# Schematic.net
KiCad netlist of a schematic drawn in EasyEDA Pro
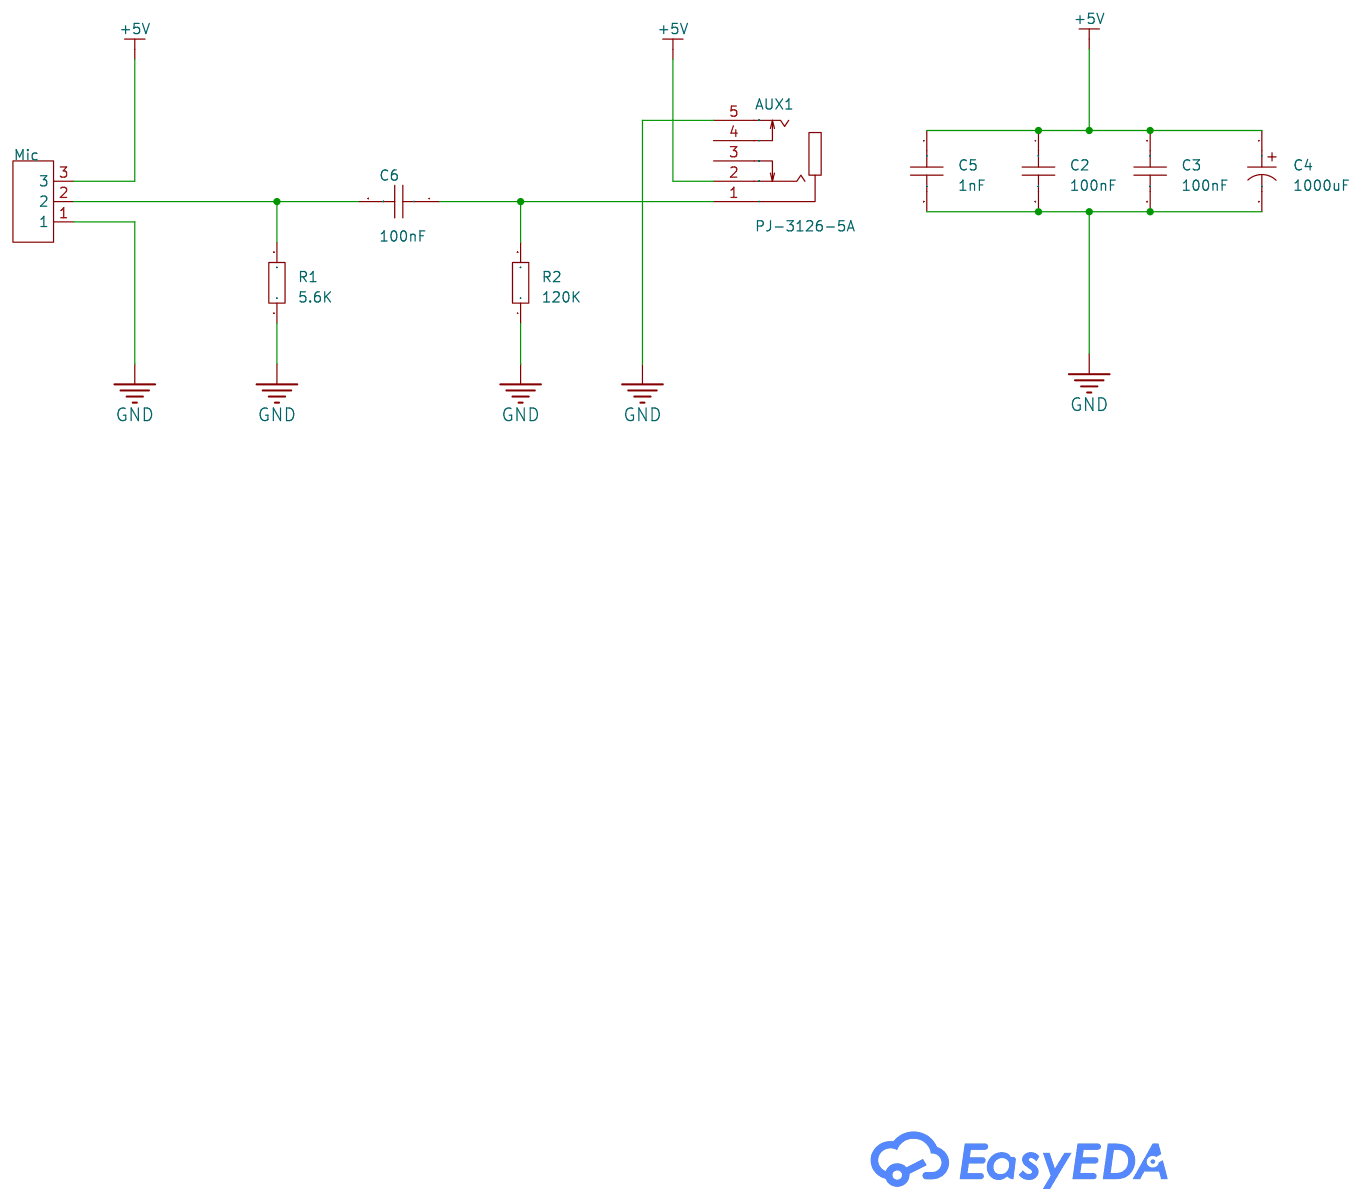
[diagram p0: schematic sheet]

(export (version "E")
  (design (tool "Eeschema 10.0.6"))
  (components
    (comp (ref "AUX1")
      (value "PJ-3126-5A")
      (footprint "easyedapro:AUDIO-TH_PJ-3126-5A")
      (fields (field (name "Manufacturer") "韩国韩荣"))
      (libsource (lib "easyedapro") (part "PJ-3126-5A"))
    )
    (comp (ref "C2")
      (value "100nF")
      (footprint "easyedapro:C0805")
      (libsource (lib "easyedapro") (part "CAP"))
    )
    (comp (ref "C3")
      (value "100nF")
      (footprint "easyedapro:C0805")
      (libsource (lib "easyedapro") (part "CAP"))
    )
    (comp (ref "C4")
      (value "1000uF")
      (footprint "easyedapro:CAP-TH_BD10.0-P5.00-D0.6-FD")
      (fields
        (field (name "Manufacturer Part") "RD1C108M10016PA160")
        (field (name "Manufacturer") "SAMWHA(三和)")
      )
      (libsource (lib "easyedapro") (part "RD1C108M10016PA160"))
    )
    (comp (ref "C5") (value "1nF") (footprint "easyedapro:C0805") (libsource (lib "easyedapro") (part "CAP")))
    (comp (ref "C6")
      (value "100nF")
      (footprint "easyedapro:C0805")
      (libsource (lib "easyedapro") (part "CAP"))
    )
    (comp (ref "Mic")
      (value "~")
      (footprint "easyedapro:HDR-TH_3P-P2.54-V-F")
      (libsource (lib "easyedapro") (part "PM254V-11-03-H85"))
    )
    (comp (ref "R1")
      (value "5.6K")
      (footprint "easyedapro:R0805")
      (libsource (lib "easyedapro") (part "Res"))
    )
    (comp (ref "R2")
      (value "120K")
      (footprint "easyedapro:R0805")
      (libsource (lib "easyedapro") (part "Res"))
    )
  )
  (nets
    (net (code "1") (name "+5V") (class "Default")
      (node (ref "AUX1") (pin "2") (pinfunction "2_2") (pintype "unspecified"))
      (node (ref "C2") (pin "1") (pinfunction "1_1") (pintype "input"))
      (node (ref "C3") (pin "1") (pinfunction "1_1") (pintype "input"))
      (node (ref "C4") (pin "1") (pinfunction "1_1") (pintype "input"))
      (node (ref "C5") (pin "1") (pinfunction "1_1") (pintype "input"))
      (node (ref "Mic") (pin "3") (pinfunction "3_3") (pintype "unspecified"))
    )
    (net (code "2") (name "GND") (class "Default")
      (node (ref "AUX1") (pin "5") (pinfunction "5_5") (pintype "unspecified"))
      (node (ref "C2") (pin "2") (pinfunction "2_2") (pintype "input"))
      (node (ref "C3") (pin "2") (pinfunction "2_2") (pintype "input"))
      (node (ref "C4") (pin "2") (pinfunction "2_2") (pintype "input"))
      (node (ref "C5") (pin "2") (pinfunction "2_2") (pintype "input"))
      (node (ref "Mic") (pin "1") (pinfunction "1_1") (pintype "unspecified"))
      (node (ref "R1") (pin "1") (pinfunction "1_1") (pintype "input"))
      (node (ref "R2") (pin "1") (pinfunction "1_1") (pintype "input"))
    )
    (net (code "3") (name "Net-(AUX1-Pad1)") (class "Default")
      (node (ref "AUX1") (pin "1") (pinfunction "1_1") (pintype "unspecified"))
      (node (ref "C6") (pin "1") (pinfunction "1_1") (pintype "input"))
      (node (ref "R2") (pin "2") (pinfunction "2_2") (pintype "input"))
    )
    (net (code "4") (name "Net-(C6-Pad2)") (class "Default")
      (node (ref "C6") (pin "2") (pinfunction "2_2") (pintype "input"))
      (node (ref "Mic") (pin "2") (pinfunction "2_2") (pintype "unspecified"))
      (node (ref "R1") (pin "2") (pinfunction "2_2") (pintype "input"))
    )
    (net (code "5") (name "unconnected-(AUX1-Pad3)") (class "Default")
      (node (ref "AUX1") (pin "3") (pinfunction "3_3") (pintype "unspecified"))
    )
    (net (code "6") (name "unconnected-(AUX1-Pad4)") (class "Default")
      (node (ref "AUX1") (pin "4") (pinfunction "4_4") (pintype "unspecified"))
    )
  )
)
